# MCUs_STM32.net
KiCad netlist of a schematic drawn in Altium Designer
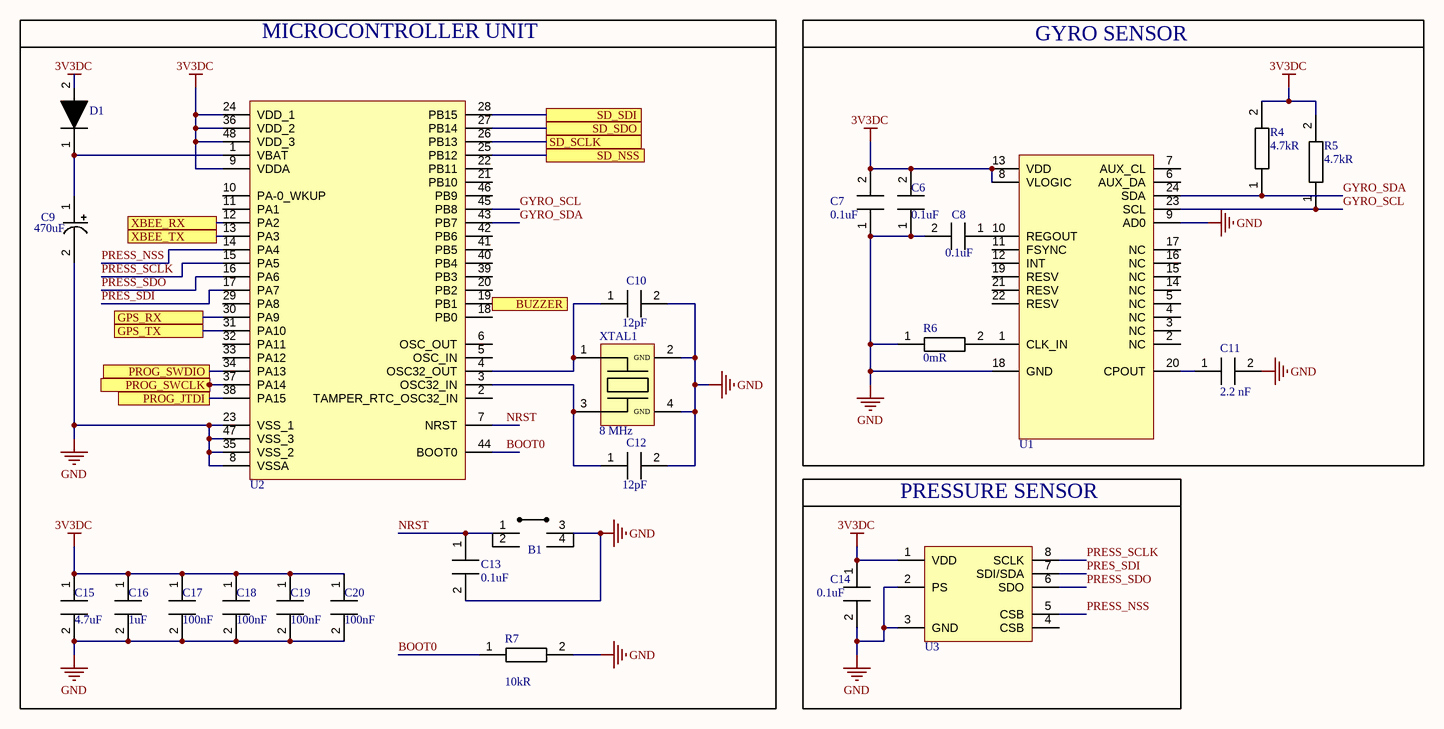
[diagram p0: MCUs_STM32.SchDoc]

(export (version "E")
  (design (tool "Eeschema 10.0.6"))
  (components
    (comp (ref "B1")
      (value "B_D6R90 F1 LFS")
      (footprint "PBUTTON_OFFMOM")
      (libsource (lib "AHMET_CAN_KARACAN") (part "B_D6R90 F1 LFS"))
    )
    (comp (ref "C6")
      (value "0.1uF")
      (footprint "CAP_1206")
      (description "Multilayer Ceramic Capacitor, 0.1 uF, 25 V, ± 10%, X7R, 1206 [3216 Metric]")
      (fields
        (field (name "MANUFACTURER") "KEMET")
        (field (name "MANUFACTURER PART NUMBER") "C1206C104K3RACTU")
        (field (name "DESIGNED BY") "Ahmet Can")
      )
      (libsource (lib "AHMET_CAN_KARACAN") (part "CAP CER 0.1uF 1206"))
    )
    (comp (ref "C7")
      (value "0.1uF")
      (footprint "CAP_1206")
      (description "Multilayer Ceramic Capacitor, 0.1 uF, 25 V, ± 10%, X7R, 1206 [3216 Metric]")
      (fields
        (field (name "MANUFACTURER") "KEMET")
        (field (name "MANUFACTURER PART NUMBER") "C1206C104K3RACTU")
        (field (name "DESIGNED BY") "Ahmet Can")
      )
      (libsource (lib "AHMET_CAN_KARACAN") (part "CAP CER 0.1uF 1206"))
    )
    (comp (ref "C8")
      (value "0.1uF")
      (footprint "CAP_1206")
      (description "Multilayer Ceramic Capacitor, 0.1 uF, 25 V, ± 10%, X7R, 1206 [3216 Metric]")
      (fields
        (field (name "MANUFACTURER") "KEMET")
        (field (name "MANUFACTURER PART NUMBER") "C1206C104K3RACTU")
        (field (name "DESIGNED BY") "Ahmet Can")
      )
      (libsource (lib "AHMET_CAN_KARACAN") (part "CAP CER 0.1uF 1206"))
    )
    (comp (ref "C9")
      (value "470uF")
      (footprint "CAP_RADIAL_D10_P5")
      (description "Cap, 470UF, 50V, Alu Elec, Radial, Through Hole")
      (fields
        (field (name "MANUFACTURER") "KEMET")
        (field (name "MANUFACTURER PART NUMBER") "ESH477M050AH4AA")
        (field (name "DESIGNED BY") "Ahmet Can")
      )
      (libsource (lib "AHMET_CAN_KARACAN") (part "CAP ALU ELEC 470uF"))
    )
    (comp (ref "C10")
      (value "12pF")
      (footprint "CAP_1206")
      (description "Multilayer Ceramic Capacitor, 12 pF, 50 V, ± 5%, C0G (NP0), 1206 [3216 Metric]")
      (fields
        (field (name "MANUFACTURER") "KEMET")
        (field (name "MANUFACTURER PART NUMBER") "C1206C120J5GACTU")
        (field (name "DESIGNED BY") "Ahmet Can")
      )
      (libsource (lib "AHMET_CAN_KARACAN") (part "CAP CER 12pF 1206"))
    )
    (comp (ref "C11")
      (value "2.2 nF")
      (footprint "CAP_1206")
      (description "CAP CER 2200PF 50V X7R 1206")
      (fields
        (field (name "MANUFACTURER") "Yageo")
        (field (name "MANUFACTURER PART NUMBER") "CC1206KRX7R9BB222")
      )
      (libsource (lib "AHMET_CAN_KARACAN") (part "CAP CER 2.2 nF 1206"))
    )
    (comp (ref "C12")
      (value "12pF")
      (footprint "CAP_1206")
      (description "Multilayer Ceramic Capacitor, 12 pF, 50 V, ± 5%, C0G (NP0), 1206 [3216 Metric]")
      (fields
        (field (name "MANUFACTURER") "KEMET")
        (field (name "MANUFACTURER PART NUMBER") "C1206C120J5GACTU")
        (field (name "DESIGNED BY") "Ahmet Can")
      )
      (libsource (lib "AHMET_CAN_KARACAN") (part "CAP CER 12pF 1206"))
    )
    (comp (ref "C13")
      (value "0.1uF")
      (footprint "CAP_1206")
      (description "Multilayer Ceramic Capacitor, 0.1 uF, 25 V, ± 10%, X7R, 1206 [3216 Metric]")
      (fields
        (field (name "MANUFACTURER") "KEMET")
        (field (name "MANUFACTURER PART NUMBER") "C1206C104K3RACTU")
        (field (name "DESIGNED BY") "Ahmet Can")
      )
      (libsource (lib "AHMET_CAN_KARACAN") (part "CAP CER 0.1uF 1206"))
    )
    (comp (ref "C14")
      (value "0.1uF")
      (footprint "CAP_1206")
      (description "Multilayer Ceramic Capacitor, 0.1 uF, 25 V, ± 10%, X7R, 1206 [3216 Metric]")
      (fields
        (field (name "MANUFACTURER") "KEMET")
        (field (name "MANUFACTURER PART NUMBER") "C1206C104K3RACTU")
        (field (name "DESIGNED BY") "Ahmet Can")
      )
      (libsource (lib "AHMET_CAN_KARACAN") (part "CAP CER 0.1uF 1206"))
    )
    (comp (ref "C15")
      (value "4.7uF")
      (footprint "CAP_0805")
      (description "Multilayer Ceramic Capacitor, 4.7 uF, 25 V, ± 10%, X5R, 0805 [2012 Metric]")
      (fields
        (field (name "MANUFACTURER") "Samsung")
        (field (name "MANUFACTURER PART NUMBER") "CL21A475KAQNNNE")
        (field (name "DESIGNED BY") "Ahmet Can")
      )
      (libsource (lib "AHMET_CAN_KARACAN") (part "CAP CER 4.7uF 0805"))
    )
    (comp (ref "C16")
      (value "1uF")
      (footprint "CAP_0805")
      (description "CAP CER %10 1uF 0805")
      (fields
        (field (name "MANUFACTURER") "Samsung")
        (field (name "MANUFACTURER PART NUMBER") "CL21B105KBFNNNE")
      )
      (libsource (lib "AHMET_CAN_KARACAN") (part "CAP CER 1uF 0805"))
    )
    (comp (ref "C17")
      (value "CL21B104KBCNNNC")
      (footprint "CAP_0805")
      (description "Multilayer Ceramic Capacitor, 0.1 uF, 50 V, ± 10%, X7R, 0805 [2012 Metric]")
      (fields
        (field (name "MANUFACTURER") "Samsung")
        (field (name "TOLERANCE") "10%")
        (field (name "CAPACITANCE") "100nF")
      )
      (libsource (lib "AHMET_CAN_KARACAN") (part "CAP CER 100nF 0805"))
    )
    (comp (ref "C18")
      (value "CL21B104KBCNNNC")
      (footprint "CAP_0805")
      (description "Multilayer Ceramic Capacitor, 0.1 uF, 50 V, ± 10%, X7R, 0805 [2012 Metric]")
      (fields
        (field (name "MANUFACTURER") "Samsung")
        (field (name "TOLERANCE") "10%")
        (field (name "CAPACITANCE") "100nF")
      )
      (libsource (lib "AHMET_CAN_KARACAN") (part "CAP CER 100nF 0805"))
    )
    (comp (ref "C19")
      (value "CL21B104KBCNNNC")
      (footprint "CAP_0805")
      (description "Multilayer Ceramic Capacitor, 0.1 uF, 50 V, ± 10%, X7R, 0805 [2012 Metric]")
      (fields
        (field (name "MANUFACTURER") "Samsung")
        (field (name "TOLERANCE") "10%")
        (field (name "CAPACITANCE") "100nF")
      )
      (libsource (lib "AHMET_CAN_KARACAN") (part "CAP CER 100nF 0805"))
    )
    (comp (ref "C20")
      (value "CL21B104KBCNNNC")
      (footprint "CAP_0805")
      (description "Multilayer Ceramic Capacitor, 0.1 uF, 50 V, ± 10%, X7R, 0805 [2012 Metric]")
      (fields
        (field (name "MANUFACTURER") "Samsung")
        (field (name "TOLERANCE") "10%")
        (field (name "CAPACITANCE") "100nF")
      )
      (libsource (lib "AHMET_CAN_KARACAN") (part "CAP CER 100nF 0805"))
    )
    (comp (ref "D1")
      (value "1N4148WS")
      (footprint "SOD_323_F")
      (description "Diode Ultra Fast Recovery Rectifier 75V 0.15A 2-Pin SOD-323F T/R")
      (fields
        (field (name "MANUFACTURER") "ON Semiconductor / Fairchild")
        (field (name "DESIGNED BY") "Ahmet Can")
      )
      (libsource (lib "AHMET_CAN_KARACAN") (part "DIO_1N4148WS"))
    )
    (comp (ref "R4")
      (value "4.7kR")
      (footprint "RE_1206")
      (description "SMD Chip Resistor, 4.7 kOhm, ± 1%, 250 mW, 1206 [3216 Metric], Thick Film, General Purpose")
      (fields
        (field (name "MANUFACTURER") "Yageo")
        (field (name "MANUFACTURER PART NUMBER") "RC1206FR-074K7L")
        (field (name "DESIGNED BY") "Ahmet Can")
      )
      (libsource (lib "AHMET_CAN_KARACAN") (part "RES 4K7 1206"))
    )
    (comp (ref "R5")
      (value "4.7kR")
      (footprint "RE_1206")
      (description "SMD Chip Resistor, 4.7 kOhm, ± 1%, 250 mW, 1206 [3216 Metric], Thick Film, General Purpose")
      (fields
        (field (name "MANUFACTURER") "Yageo")
        (field (name "MANUFACTURER PART NUMBER") "RC1206FR-074K7L")
        (field (name "DESIGNED BY") "Ahmet Can")
      )
      (libsource (lib "AHMET_CAN_KARACAN") (part "RES 4K7 1206"))
    )
    (comp (ref "R6")
      (value "0mR")
      (footprint "RE_0603")
      (description "Zero Ohm Resistor, Jumper, 0603 [1608 Metric], Thick Film, 100 mW, 1 A, Surface Mount")
      (fields
        (field (name "MANUFACTURER") "Yageo")
        (field (name "MANUFACTURER PART NUMBER") "RC0603JR-070RL")
        (field (name "DESIGNED BY") "Ahmet Can")
      )
      (libsource (lib "AHMET_CAN_KARACAN") (part "RES 0K 0603"))
    )
    (comp (ref "R7")
      (value "10kR")
      (footprint "RE_1206")
      (description "SMD Chip Resistor, 10 kOhm, ± 1%, 250 mW, 1206 [3216 Metric], Thick Film, General Purpose")
      (fields
        (field (name "MANUFACTURER") "Yageo")
        (field (name "MANUFACTURER PART NUMBER") "RC1206FR-0710KL")
        (field (name "DESIGNED BY") "Ahmet Can")
      )
      (libsource (lib "AHMET_CAN_KARACAN") (part "RES 10K 1206"))
    )
    (comp (ref "U1")
      (value "MPU6050")
      (footprint "QFN_24")
      (description "IMU ACCEL/GYRO 3-AXIS I2C 24QFN")
      (fields
        (field (name "MANUFACTURER") "TDK InvenSense")
        (field (name "MANUFACTURER PART NUMBER") "MPU-6050")
        (field (name "DESIGNED BY") "Ahmet Can")
      )
      (libsource (lib "AHMET_CAN_KARACAN") (part "U_MPU6050"))
    )
    (comp (ref "U2")
      (value "STM32F103C8T6")
      (footprint "LQGP48-STM")
      (description "ARM Cortex-M3 STM32 F1 Microcontroller 32-Bit 72MHz 64kB FLASH LQFP48 STM32F103C8T6")
      (fields (field (name "MANUFACTURER") "STMicroelectronics") (field (name "DESIGNED BY") "Ahmet Can"))
      (libsource (lib "AHMET_CAN_KARACAN") (part "U_STM32F103C8T6"))
    )
    (comp (ref "U3")
      (value "MS560702BA03-50")
      (footprint "8-SMD_MS560702BA03")
      (description "Board Mount Pressure Sensor 0.01bar to 1.2bar Absolute 8-Pin QFN T/R")
      (fields (field (name "MANUFACTURER") "TE Connectivity") (field (name "DESIGNED BY") "Ahmet Can"))
      (libsource (lib "AHMET_CAN_KARACAN") (part "U_MS560702BA03-50"))
    )
    (comp (ref "XTAL1")
      (value "8 MHz")
      (footprint "4-SMD, No Lead")
      (description "8 MHz ±10ppm Crystal 10pF 100 Ohms 4-SMD, No Lead")
      (fields
        (field (name "MANUFACTURER") "ECS International")
        (field (name "MANUFACTURER PART NUMBER") "ECS-80-10-30B-CKM-TR")
      )
      (libsource (lib "AHMET_CAN_KARACAN") (part "XTAL_CRYSTAL_8 MHz"))
    )
  )
  (nets
    (net (code "1") (name "/BOOT0") (class "Default")
      (node (ref "R7") (pin "1") (pintype "passive"))
      (node (ref "U2") (pin "44") (pinfunction "BOOT0_44") (pintype "passive"))
    )
    (net (code "2") (name "/BUZZER") (class "Default")
      (node (ref "U2") (pin "19") (pinfunction "PB1_19") (pintype "passive"))
    )
    (net (code "3") (name "/GPS_RX") (class "Default")
      (node (ref "U2") (pin "30") (pinfunction "PA9_30") (pintype "passive"))
    )
    (net (code "4") (name "/GPS_TX") (class "Default")
      (node (ref "U2") (pin "31") (pinfunction "PA10_31") (pintype "passive"))
    )
    (net (code "5") (name "/GYRO_SCL") (class "Default")
      (node (ref "R5") (pin "1") (pintype "passive"))
      (node (ref "U1") (pin "23") (pinfunction "SCL_23") (pintype "passive"))
      (node (ref "U2") (pin "45") (pinfunction "PB8_45") (pintype "passive"))
    )
    (net (code "6") (name "/GYRO_SDA") (class "Default")
      (node (ref "R4") (pin "1") (pintype "passive"))
      (node (ref "U1") (pin "24") (pinfunction "SDA_24") (pintype "passive"))
      (node (ref "U2") (pin "43") (pinfunction "PB7_43") (pintype "passive"))
    )
    (net (code "7") (name "/NRST") (class "Default")
      (node (ref "B1") (pin "1") (pintype "passive"))
      (node (ref "C13") (pin "1") (pintype "passive"))
      (node (ref "U2") (pin "7") (pinfunction "NRST_7") (pintype "passive"))
    )
    (net (code "8") (name "/PRESS_NSS") (class "Default")
      (node (ref "U2") (pin "14") (pinfunction "PA4_14") (pintype "passive"))
      (node (ref "U3") (pin "5") (pinfunction "CSB_5") (pintype "passive"))
    )
    (net (code "9") (name "/PRESS_SCLK") (class "Default")
      (node (ref "U2") (pin "15") (pinfunction "PA5_15") (pintype "passive"))
      (node (ref "U3") (pin "8") (pinfunction "SCLK_8") (pintype "passive"))
    )
    (net (code "10") (name "/PRESS_SDO") (class "Default")
      (node (ref "U2") (pin "16") (pinfunction "PA6_16") (pintype "passive"))
      (node (ref "U3") (pin "6") (pinfunction "SDO_6") (pintype "passive"))
    )
    (net (code "11") (name "/PRES_SDI") (class "Default")
      (node (ref "U2") (pin "17") (pinfunction "PA7_17") (pintype "passive"))
      (node (ref "U3") (pin "7") (pinfunction "SDI/SDA_7") (pintype "passive"))
    )
    (net (code "12") (name "/PROG_JTDI") (class "Default")
      (node (ref "U2") (pin "38") (pinfunction "PA15_38") (pintype "passive"))
    )
    (net (code "13") (name "/PROG_SWCLK") (class "Default")
      (node (ref "U2") (pin "37") (pinfunction "PA14_37") (pintype "passive"))
    )
    (net (code "14") (name "/PROG_SWDIO") (class "Default")
      (node (ref "U2") (pin "34") (pinfunction "PA13_34") (pintype "passive"))
    )
    (net (code "15") (name "/SD_NSS") (class "Default")
      (node (ref "U2") (pin "25") (pinfunction "PB12_25") (pintype "passive"))
    )
    (net (code "16") (name "/SD_SCLK") (class "Default")
      (node (ref "U2") (pin "26") (pinfunction "PB13_26") (pintype "passive"))
    )
    (net (code "17") (name "/SD_SDI") (class "Default")
      (node (ref "U2") (pin "28") (pinfunction "PB15_28") (pintype "passive"))
    )
    (net (code "18") (name "/SD_SDO") (class "Default")
      (node (ref "U2") (pin "27") (pinfunction "PB14_27") (pintype "passive"))
    )
    (net (code "19") (name "/XBEE_RX") (class "Default")
      (node (ref "U2") (pin "12") (pinfunction "PA2_12") (pintype "passive"))
    )
    (net (code "20") (name "/XBEE_TX") (class "Default")
      (node (ref "U2") (pin "13") (pinfunction "PA3_13") (pintype "passive"))
    )
    (net (code "21") (name "3V3DC") (class "Default")
      (node (ref "C14") (pin "1") (pintype "passive"))
      (node (ref "C15") (pin "1") (pintype "passive"))
      (node (ref "C16") (pin "1") (pintype "passive"))
      (node (ref "C17") (pin "1") (pintype "passive"))
      (node (ref "C18") (pin "1") (pintype "passive"))
      (node (ref "C19") (pin "1") (pintype "passive"))
      (node (ref "C20") (pin "1") (pintype "passive"))
      (node (ref "C6") (pin "2") (pintype "passive"))
      (node (ref "C7") (pin "2") (pintype "passive"))
      (node (ref "D1") (pin "2") (pintype "passive"))
      (node (ref "R4") (pin "2") (pintype "passive"))
      (node (ref "R5") (pin "2") (pintype "passive"))
      (node (ref "U1") (pin "13") (pinfunction "VDD_13") (pintype "passive"))
      (node (ref "U1") (pin "8") (pinfunction "VLOGIC_8") (pintype "passive"))
      (node (ref "U2") (pin "24") (pinfunction "VDD_1_24") (pintype "passive"))
      (node (ref "U2") (pin "36") (pinfunction "VDD_2_36") (pintype "passive"))
      (node (ref "U2") (pin "48") (pinfunction "VDD_3_48") (pintype "passive"))
      (node (ref "U2") (pin "9") (pinfunction "VDDA_9") (pintype "passive"))
      (node (ref "U3") (pin "1") (pinfunction "VDD_1") (pintype "passive"))
    )
    (net (code "22") (name "GND") (class "Default")
      (node (ref "B1") (pin "3") (pintype "passive"))
      (node (ref "C10") (pin "2") (pintype "passive"))
      (node (ref "C11") (pin "2") (pintype "passive"))
      (node (ref "C12") (pin "2") (pintype "passive"))
      (node (ref "C13") (pin "2") (pintype "passive"))
      (node (ref "C14") (pin "2") (pintype "passive"))
      (node (ref "C15") (pin "2") (pintype "passive"))
      (node (ref "C16") (pin "2") (pintype "passive"))
      (node (ref "C17") (pin "2") (pintype "passive"))
      (node (ref "C18") (pin "2") (pintype "passive"))
      (node (ref "C19") (pin "2") (pintype "passive"))
      (node (ref "C20") (pin "2") (pintype "passive"))
      (node (ref "C6") (pin "1") (pintype "passive"))
      (node (ref "C7") (pin "1") (pintype "passive"))
      (node (ref "C8") (pin "2") (pintype "passive"))
      (node (ref "C9") (pin "2") (pintype "passive"))
      (node (ref "R6") (pin "1") (pintype "passive"))
      (node (ref "R7") (pin "2") (pintype "passive"))
      (node (ref "U1") (pin "18") (pinfunction "GND_18") (pintype "passive"))
      (node (ref "U1") (pin "9") (pinfunction "AD0_9") (pintype "passive"))
      (node (ref "U2") (pin "23") (pinfunction "VSS_1_23") (pintype "passive"))
      (node (ref "U2") (pin "35") (pinfunction "VSS_2_35") (pintype "passive"))
      (node (ref "U2") (pin "47") (pinfunction "VSS_3_47") (pintype "passive"))
      (node (ref "U2") (pin "8") (pinfunction "VSSA_8") (pintype "passive"))
      (node (ref "U3") (pin "2") (pinfunction "PS_2") (pintype "passive"))
      (node (ref "U3") (pin "3") (pinfunction "GND_3") (pintype "passive"))
      (node (ref "XTAL1") (pin "2") (pinfunction "GND_2") (pintype "passive"))
      (node (ref "XTAL1") (pin "4") (pinfunction "GND_4") (pintype "passive"))
    )
    (net (code "23") (name "Net-(U1-CLK_IN)") (class "Default")
      (node (ref "R6") (pin "2") (pintype "passive"))
      (node (ref "U1") (pin "1") (pinfunction "CLK_IN_1") (pintype "passive"))
    )
    (net (code "24") (name "Net-(U1-CPOUT)") (class "Default")
      (node (ref "C11") (pin "1") (pintype "passive"))
      (node (ref "U1") (pin "20") (pinfunction "CPOUT_20") (pintype "passive"))
    )
    (net (code "25") (name "Net-(U1-REGOUT)") (class "Default")
      (node (ref "C8") (pin "1") (pintype "passive"))
      (node (ref "U1") (pin "10") (pinfunction "REGOUT_10") (pintype "passive"))
    )
    (net (code "26") (name "Net-(U2-OSC32_IN)") (class "Default")
      (node (ref "C12") (pin "1") (pintype "passive"))
      (node (ref "U2") (pin "3") (pinfunction "OSC32_IN_3") (pintype "passive"))
      (node (ref "XTAL1") (pin "3") (pintype "passive"))
    )
    (net (code "27") (name "Net-(U2-OSC32_OUT)") (class "Default")
      (node (ref "C10") (pin "1") (pintype "passive"))
      (node (ref "U2") (pin "4") (pinfunction "OSC32_OUT_4") (pintype "passive"))
      (node (ref "XTAL1") (pin "1") (pintype "passive"))
    )
    (net (code "28") (name "Net-(U2-VBAT)") (class "Default")
      (node (ref "C9") (pin "1") (pintype "passive"))
      (node (ref "D1") (pin "1") (pintype "passive"))
      (node (ref "U2") (pin "1") (pinfunction "VBAT_1") (pintype "passive"))
    )
    (net (code "29") (name "unconnected-(B1-Pad2)") (class "Default")
      (node (ref "B1") (pin "2") (pintype "passive"))
    )
    (net (code "30") (name "unconnected-(B1-Pad4)") (class "Default")
      (node (ref "B1") (pin "4") (pintype "passive"))
    )
    (net (code "31") (name "unconnected-(U1-AUX_CL-Pad7)") (class "Default")
      (node (ref "U1") (pin "7") (pinfunction "AUX_CL_7") (pintype "passive"))
    )
    (net (code "32") (name "unconnected-(U1-AUX_DA-Pad6)") (class "Default")
      (node (ref "U1") (pin "6") (pinfunction "AUX_DA_6") (pintype "passive"))
    )
    (net (code "33") (name "unconnected-(U1-FSYNC-Pad11)") (class "Default")
      (node (ref "U1") (pin "11") (pinfunction "FSYNC_11") (pintype "passive"))
    )
    (net (code "34") (name "unconnected-(U1-INT-Pad12)") (class "Default")
      (node (ref "U1") (pin "12") (pinfunction "INT_12") (pintype "passive"))
    )
    (net (code "35") (name "unconnected-(U1-NC-Pad2)") (class "Default")
      (node (ref "U1") (pin "2") (pinfunction "NC_2") (pintype "passive"))
    )
    (net (code "36") (name "unconnected-(U1-NC-Pad3)") (class "Default")
      (node (ref "U1") (pin "3") (pinfunction "NC_3") (pintype "passive"))
    )
    (net (code "37") (name "unconnected-(U1-NC-Pad4)") (class "Default")
      (node (ref "U1") (pin "4") (pinfunction "NC_4") (pintype "passive"))
    )
    (net (code "38") (name "unconnected-(U1-NC-Pad5)") (class "Default")
      (node (ref "U1") (pin "5") (pinfunction "NC_5") (pintype "passive"))
    )
    (net (code "39") (name "unconnected-(U1-NC-Pad14)") (class "Default")
      (node (ref "U1") (pin "14") (pinfunction "NC_14") (pintype "passive"))
    )
    (net (code "40") (name "unconnected-(U1-NC-Pad15)") (class "Default")
      (node (ref "U1") (pin "15") (pinfunction "NC_15") (pintype "passive"))
    )
    (net (code "41") (name "unconnected-(U1-NC-Pad16)") (class "Default")
      (node (ref "U1") (pin "16") (pinfunction "NC_16") (pintype "passive"))
    )
    (net (code "42") (name "unconnected-(U1-NC-Pad17)") (class "Default")
      (node (ref "U1") (pin "17") (pinfunction "NC_17") (pintype "passive"))
    )
    (net (code "43") (name "unconnected-(U1-RESV-Pad19)") (class "Default")
      (node (ref "U1") (pin "19") (pinfunction "RESV_19") (pintype "passive"))
    )
    (net (code "44") (name "unconnected-(U1-RESV-Pad21)") (class "Default")
      (node (ref "U1") (pin "21") (pinfunction "RESV_21") (pintype "passive"))
    )
    (net (code "45") (name "unconnected-(U1-RESV-Pad22)") (class "Default")
      (node (ref "U1") (pin "22") (pinfunction "RESV_22") (pintype "passive"))
    )
    (net (code "46") (name "unconnected-(U2-OSC_IN-Pad5)") (class "Default")
      (node (ref "U2") (pin "5") (pinfunction "OSC_IN_5") (pintype "passive"))
    )
    (net (code "47") (name "unconnected-(U2-OSC_OUT-Pad6)") (class "Default")
      (node (ref "U2") (pin "6") (pinfunction "OSC_OUT_6") (pintype "passive"))
    )
    (net (code "48") (name "unconnected-(U2-PA-0_WKUP-Pad10)") (class "Default")
      (node (ref "U2") (pin "10") (pinfunction "PA-0_WKUP_10") (pintype "passive"))
    )
    (net (code "49") (name "unconnected-(U2-PA1-Pad11)") (class "Default")
      (node (ref "U2") (pin "11") (pinfunction "PA1_11") (pintype "passive"))
    )
    (net (code "50") (name "unconnected-(U2-PA8-Pad29)") (class "Default")
      (node (ref "U2") (pin "29") (pinfunction "PA8_29") (pintype "passive"))
    )
    (net (code "51") (name "unconnected-(U2-PA11-Pad32)") (class "Default")
      (node (ref "U2") (pin "32") (pinfunction "PA11_32") (pintype "passive"))
    )
    (net (code "52") (name "unconnected-(U2-PA12-Pad33)") (class "Default")
      (node (ref "U2") (pin "33") (pinfunction "PA12_33") (pintype "passive"))
    )
    (net (code "53") (name "unconnected-(U2-PB0-Pad18)") (class "Default")
      (node (ref "U2") (pin "18") (pinfunction "PB0_18") (pintype "passive"))
    )
    (net (code "54") (name "unconnected-(U2-PB2-Pad20)") (class "Default")
      (node (ref "U2") (pin "20") (pinfunction "PB2_20") (pintype "passive"))
    )
    (net (code "55") (name "unconnected-(U2-PB3-Pad39)") (class "Default")
      (node (ref "U2") (pin "39") (pinfunction "PB3_39") (pintype "passive"))
    )
    (net (code "56") (name "unconnected-(U2-PB4-Pad40)") (class "Default")
      (node (ref "U2") (pin "40") (pinfunction "PB4_40") (pintype "passive"))
    )
    (net (code "57") (name "unconnected-(U2-PB5-Pad41)") (class "Default")
      (node (ref "U2") (pin "41") (pinfunction "PB5_41") (pintype "passive"))
    )
    (net (code "58") (name "unconnected-(U2-PB6-Pad42)") (class "Default")
      (node (ref "U2") (pin "42") (pinfunction "PB6_42") (pintype "passive"))
    )
    (net (code "59") (name "unconnected-(U2-PB9-Pad46)") (class "Default")
      (node (ref "U2") (pin "46") (pinfunction "PB9_46") (pintype "passive"))
    )
    (net (code "60") (name "unconnected-(U2-PB10-Pad21)") (class "Default")
      (node (ref "U2") (pin "21") (pinfunction "PB10_21") (pintype "passive"))
    )
    (net (code "61") (name "unconnected-(U2-PB11-Pad22)") (class "Default")
      (node (ref "U2") (pin "22") (pinfunction "PB11_22") (pintype "passive"))
    )
    (net (code "62") (name "unconnected-(U2-TAMPER_RTC_OSC32_IN-Pad2)") (class "Default")
      (node (ref "U2") (pin "2") (pinfunction "TAMPER_RTC_OSC32_IN_2") (pintype "passive"))
    )
    (net (code "63") (name "unconnected-(U3-CSB-Pad4)") (class "Default")
      (node (ref "U3") (pin "4") (pinfunction "CSB_4") (pintype "passive"))
    )
  )
)
